# module_tester-v02.net
KiCad netlist of a schematic drawn in EAGLE
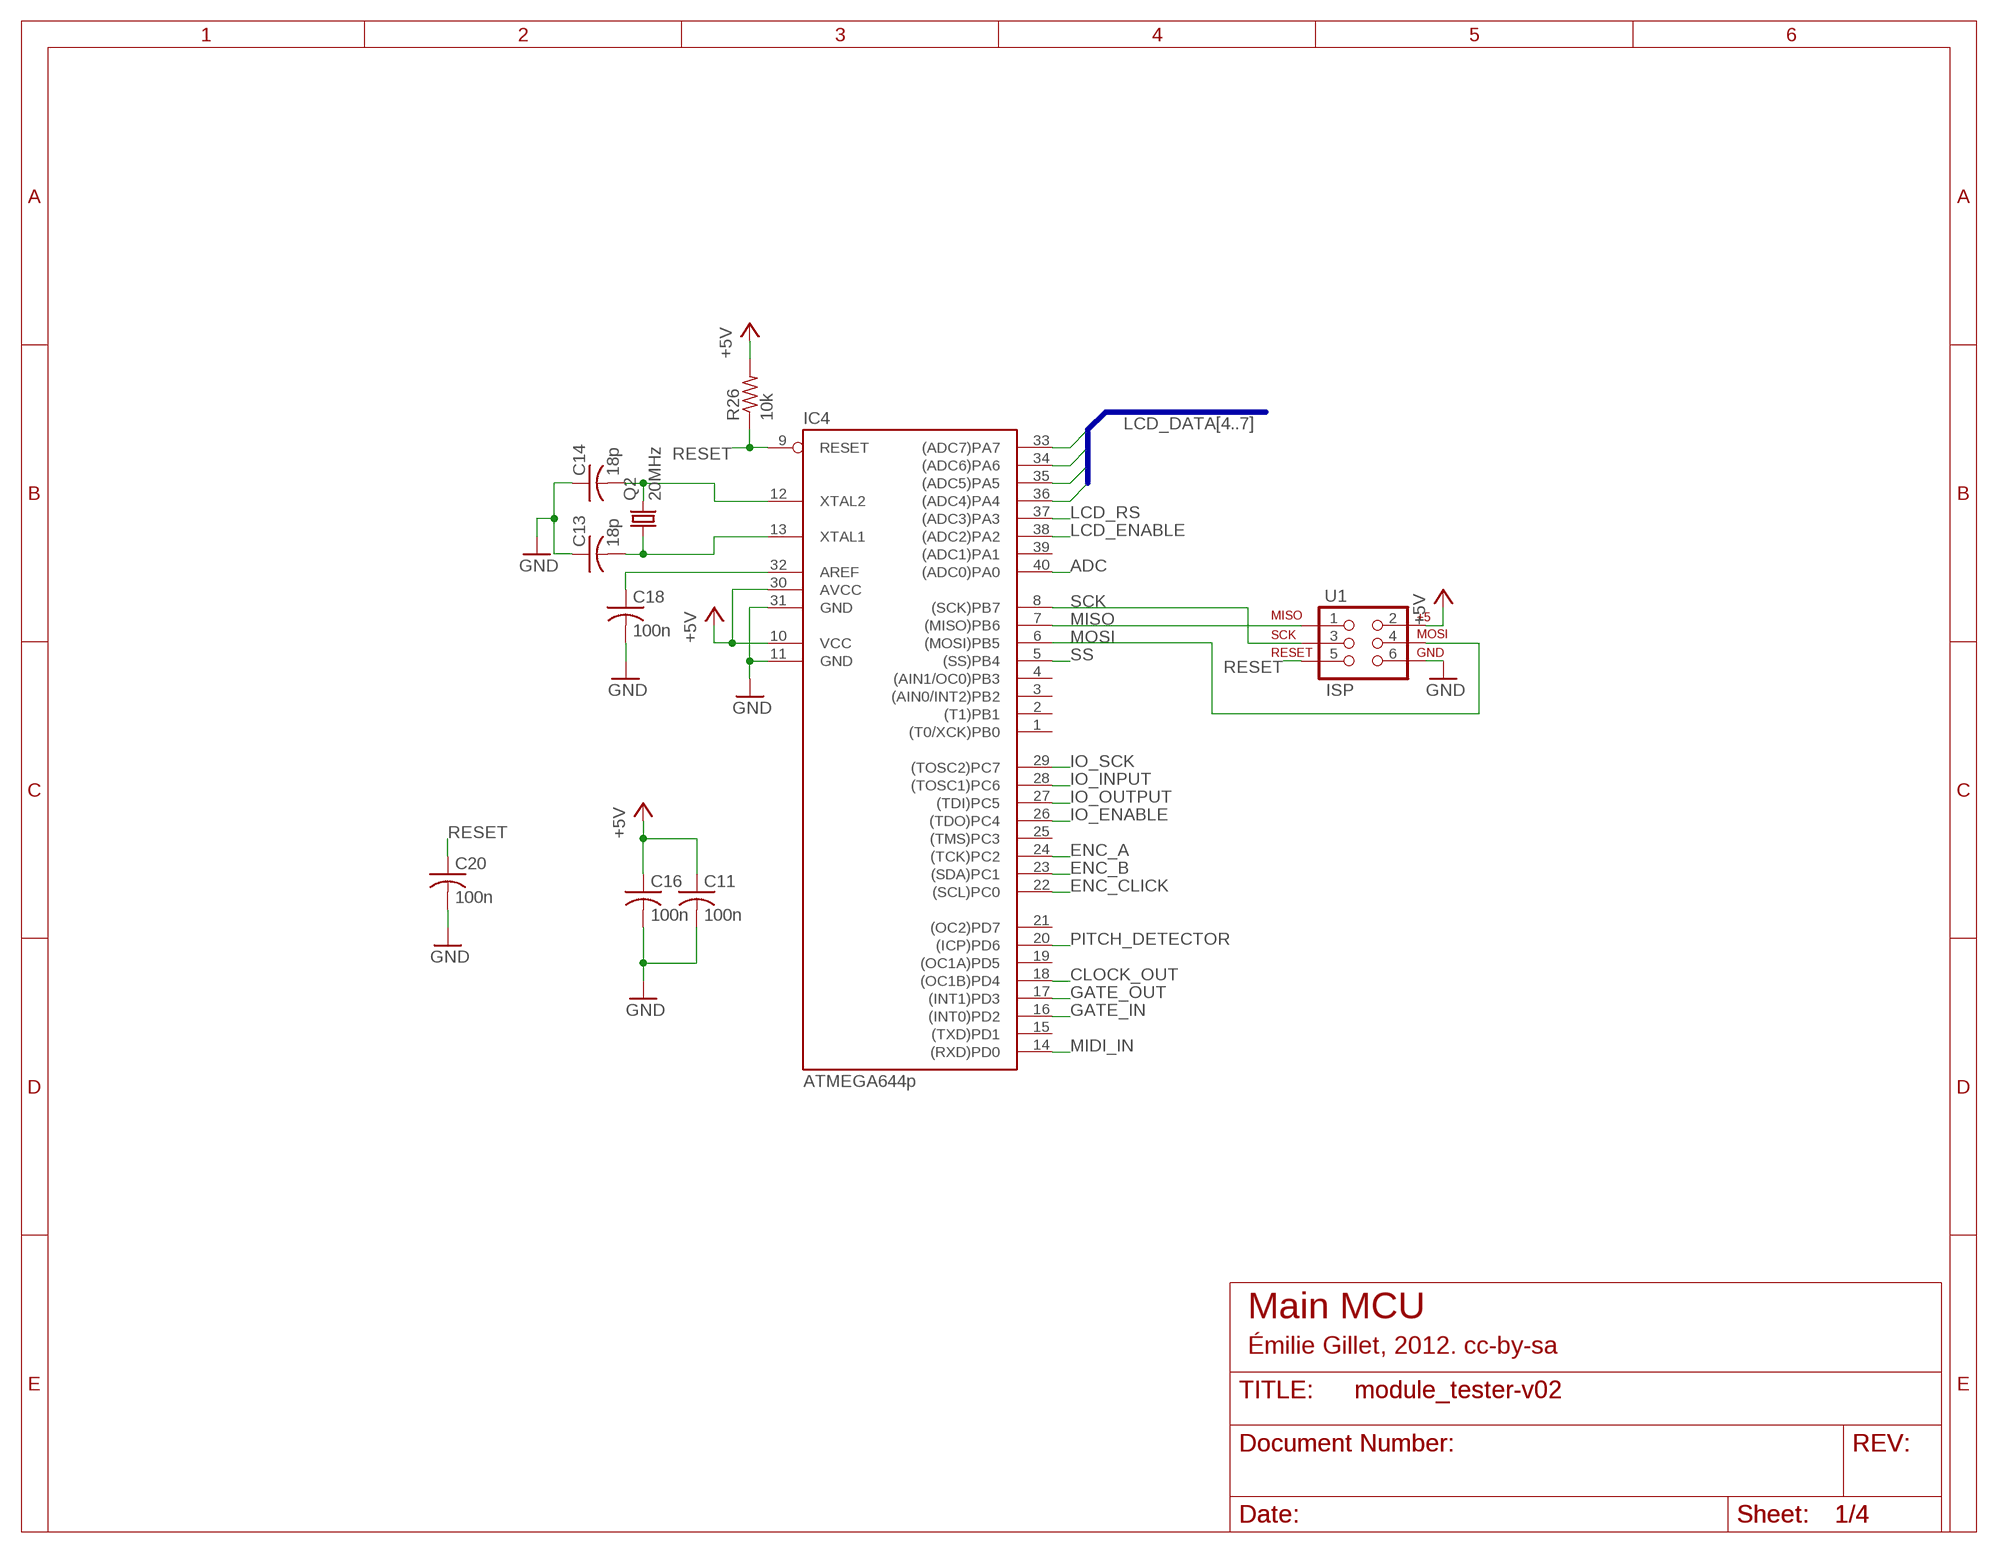
[diagram p0: schematic, sheet 1]
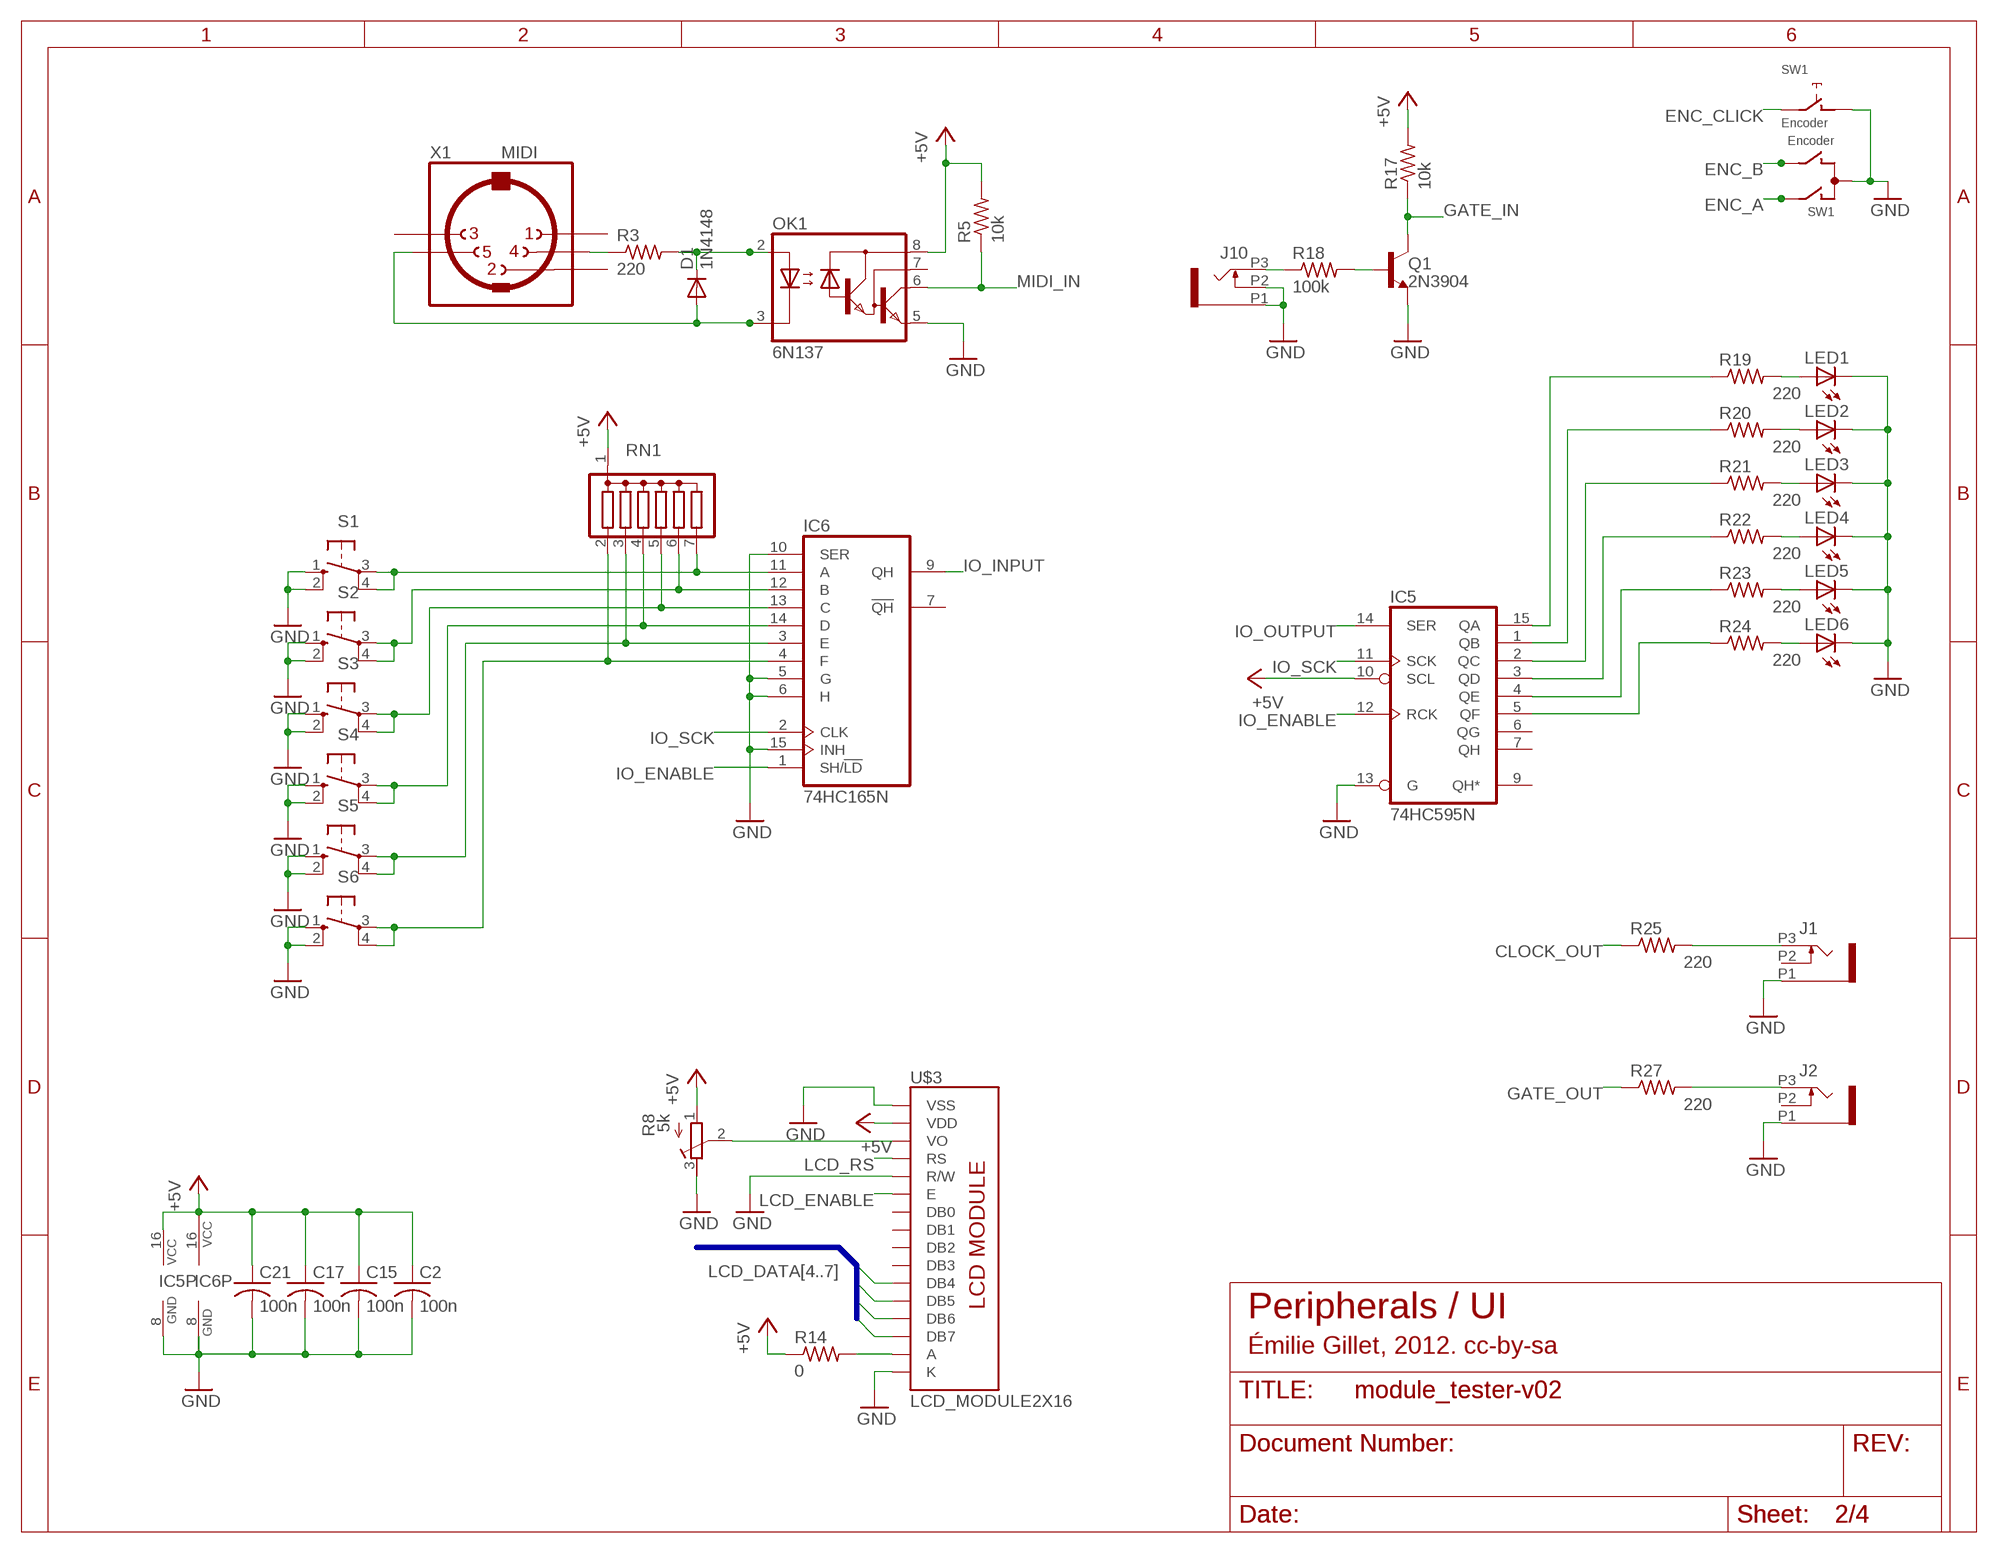
[diagram p1: schematic, sheet 2]
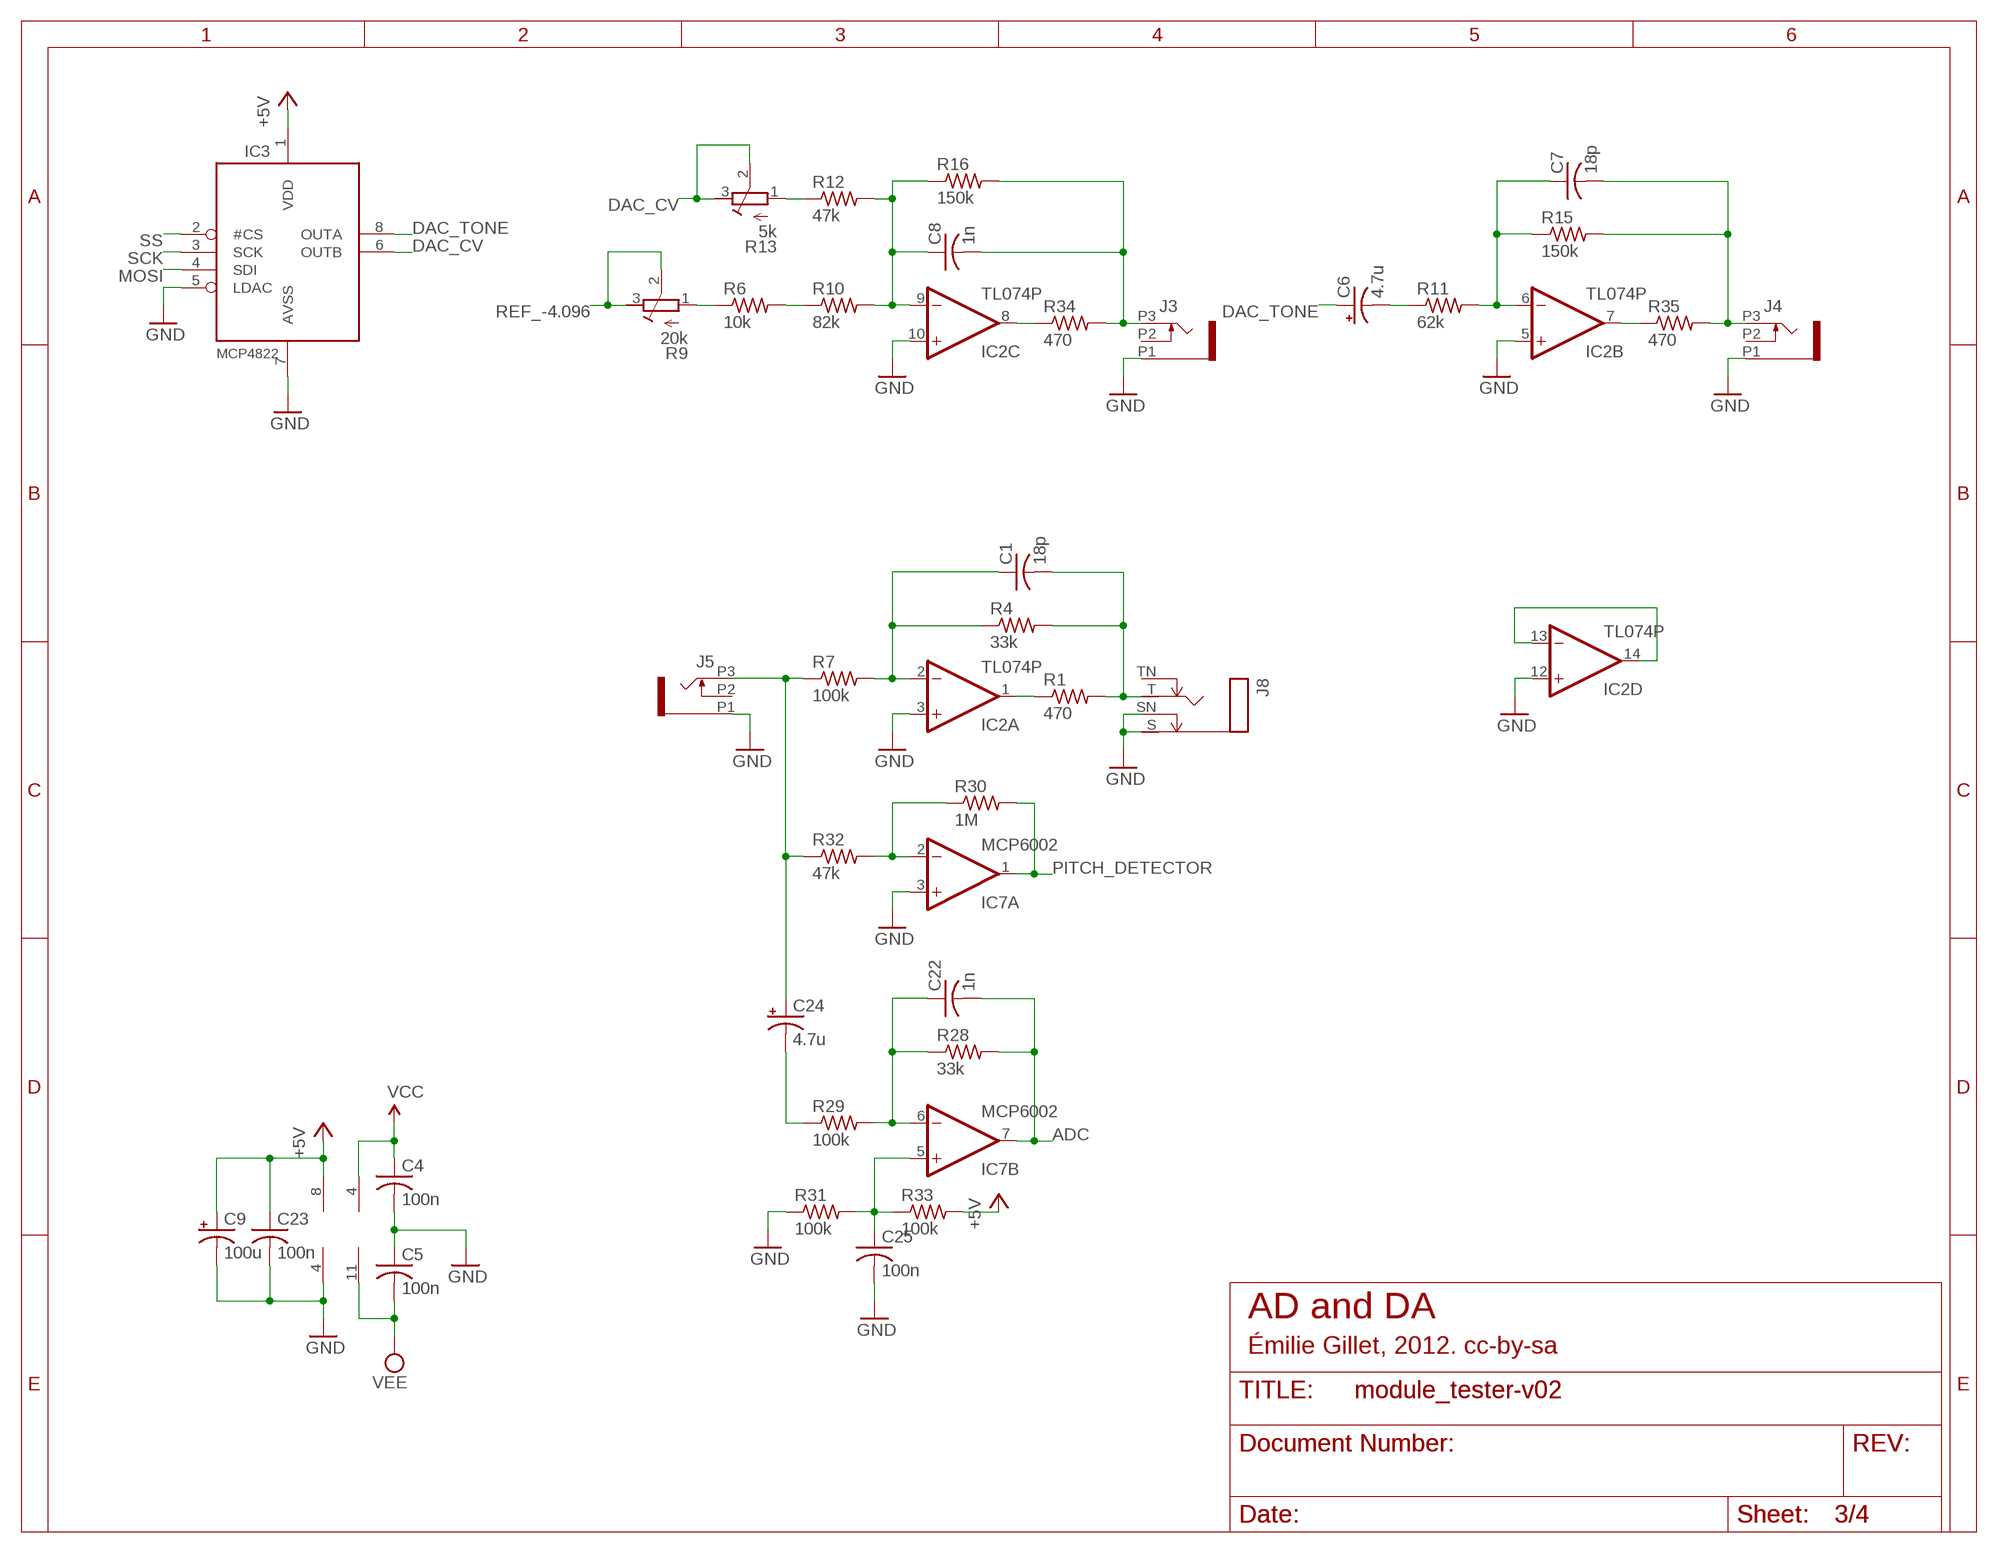
[diagram p2: schematic, sheet 3]
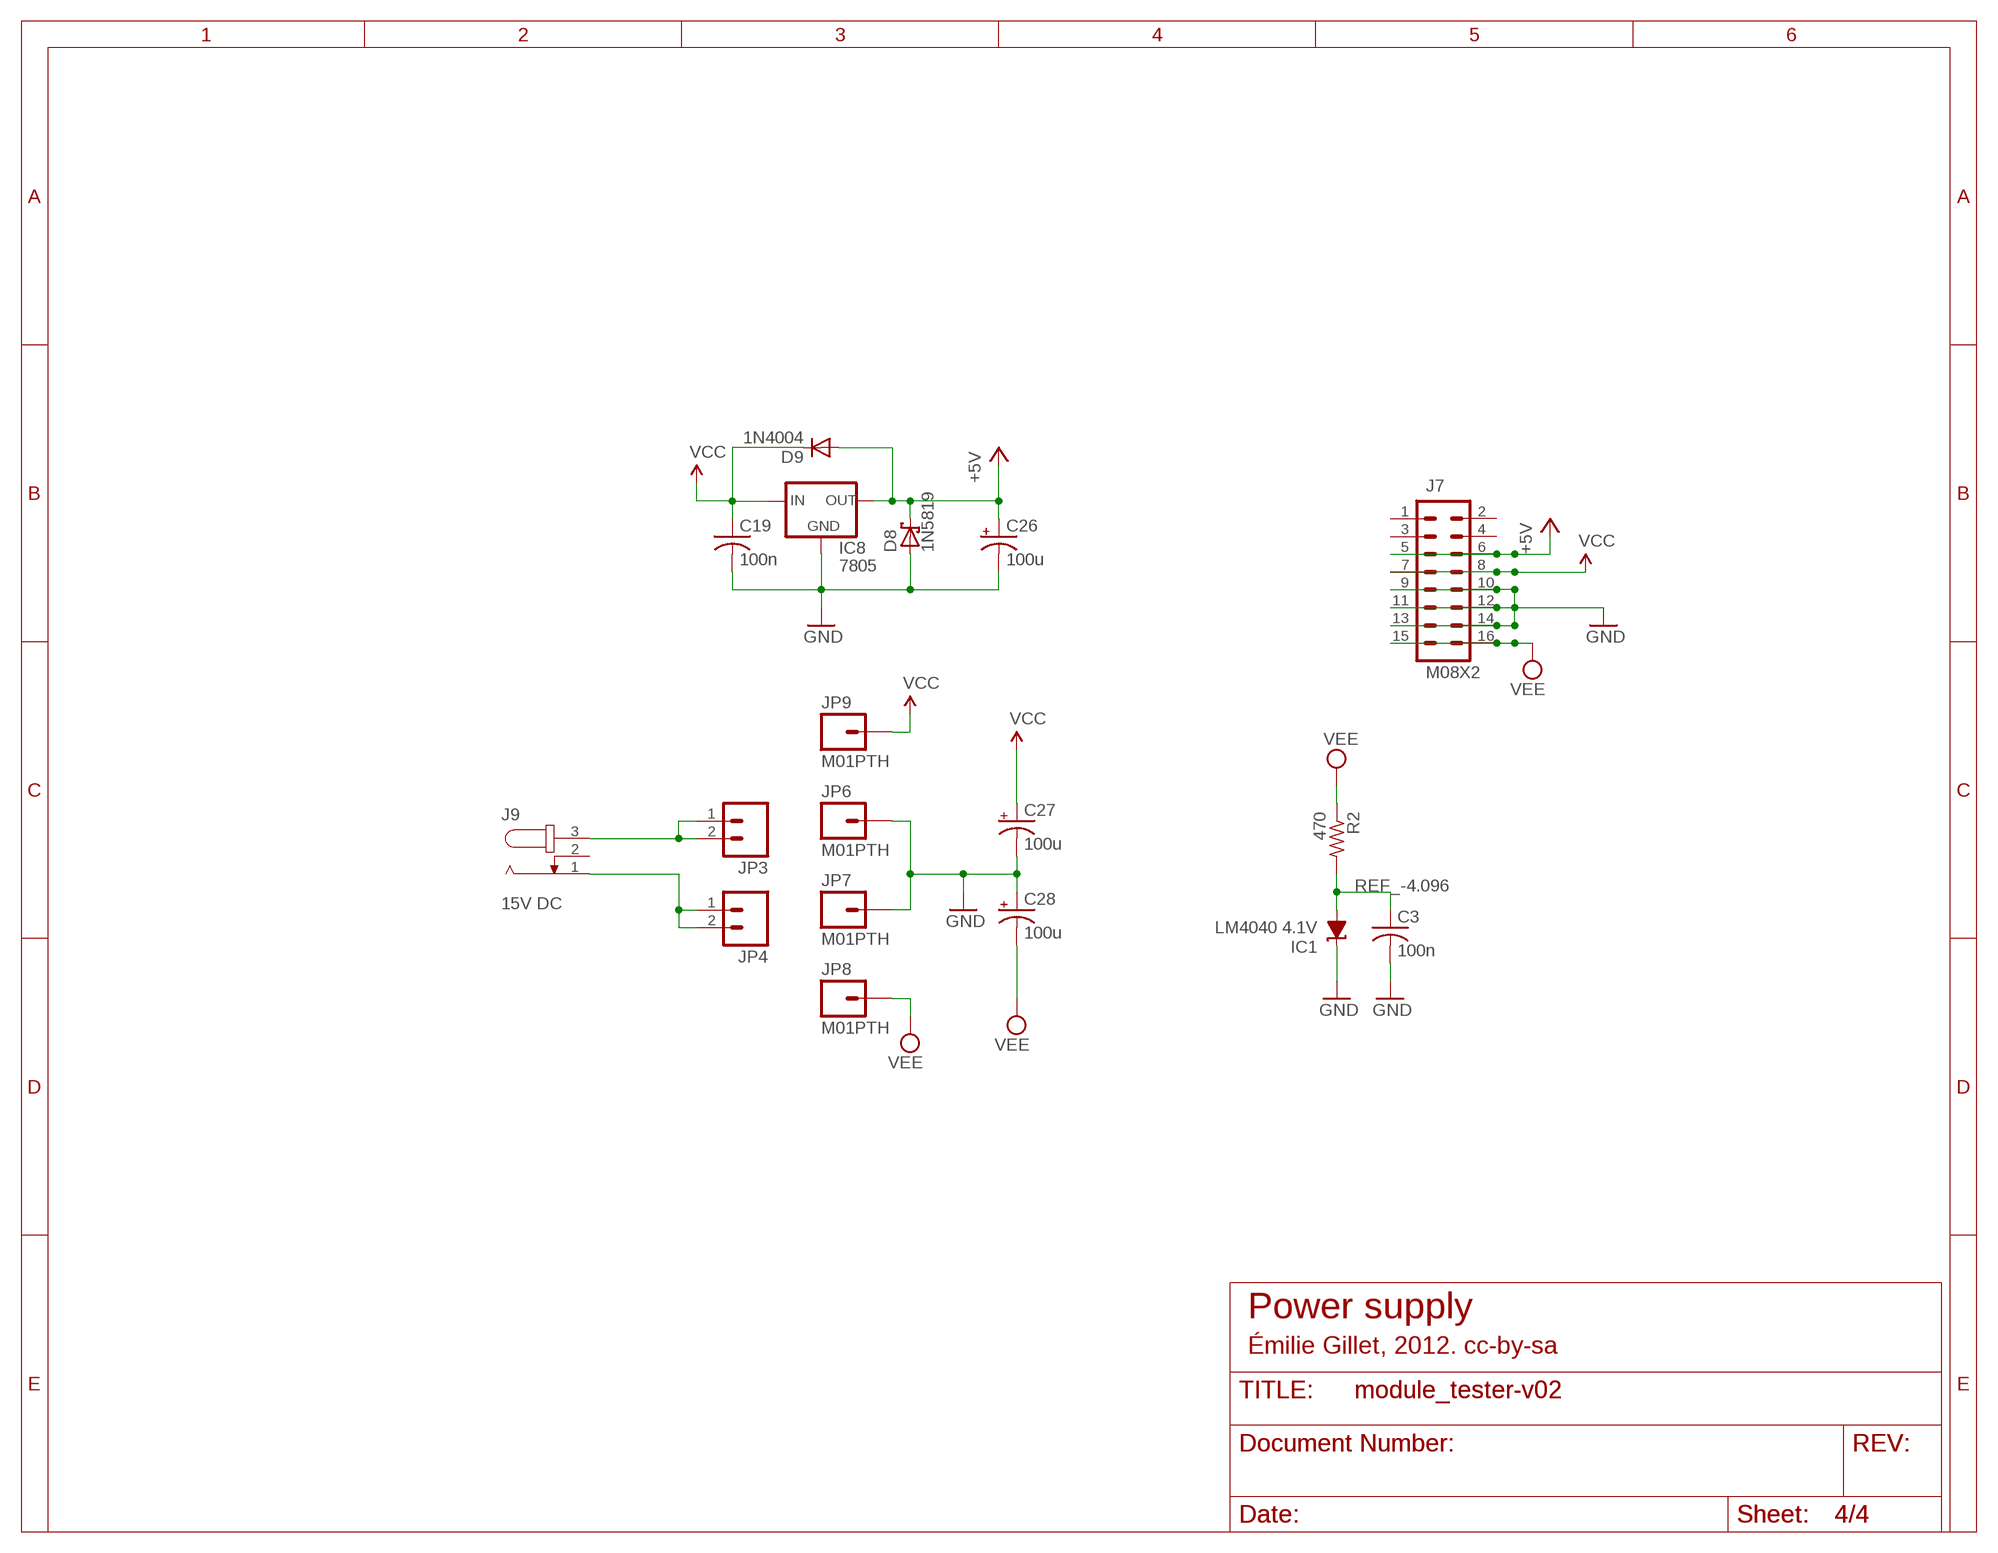
[diagram p3: schematic, sheet 4]

(export (version "E")
  (design (tool "Eeschema 10.0.6"))
  (components
    (comp (ref "C11")
      (value "100n")
      (footprint "eagle-import:C025-025X050")
      (libsource (lib "eagle-import") (part "C-US025-025X050"))
    )
    (comp (ref "C13")
      (value "18p")
      (footprint "eagle-import:C025-025X050")
      (libsource (lib "eagle-import") (part "C-US025-025X050"))
    )
    (comp (ref "C14")
      (value "18p")
      (footprint "eagle-import:C025-025X050")
      (libsource (lib "eagle-import") (part "C-US025-025X050"))
    )
    (comp (ref "C16")
      (value "100n")
      (footprint "eagle-import:C025-025X050")
      (libsource (lib "eagle-import") (part "C-US025-025X050"))
    )
    (comp (ref "C18")
      (value "100n")
      (footprint "eagle-import:C025-025X050")
      (libsource (lib "eagle-import") (part "C-US025-025X050"))
    )
    (comp (ref "C20")
      (value "100n")
      (footprint "eagle-import:C025-025X050")
      (libsource (lib "eagle-import") (part "C-US025-025X050"))
    )
    (comp (ref "IC4")
      (value "ATMEGA644p")
      (footprint "eagle-import:DIL40")
      (libsource (lib "eagle-import") (part "MEGA16-P"))
    )
    (comp (ref "Q2")
      (value "20MHz")
      (footprint "eagle-import:HC49U-V")
      (libsource (lib "eagle-import") (part "CRYSTALHC49U-V"))
    )
    (comp (ref "R26")
      (value "10k")
      (footprint "eagle-import:0204_7")
      (libsource (lib "eagle-import") (part "R-US_0204/7"))
    )
    (comp (ref "U1")
      (value "ISP")
      (footprint "eagle-import:2X3")
      (libsource (lib "eagle-import") (part "AVR_SPI_PRG_6PTH"))
    )
    (comp (ref "C3")
      (value "100n")
      (footprint "eagle-import:C025-025X050")
      (libsource (lib "eagle-import") (part "C-US025-025X050"))
    )
    (comp (ref "C19")
      (value "100n")
      (footprint "eagle-import:C025-025X050")
      (libsource (lib "eagle-import") (part "C-US025-025X050"))
    )
    (comp (ref "C26")
      (value "100u")
      (footprint "eagle-import:E2,5-7")
      (libsource (lib "eagle-import") (part "CPOL-USE2.5-7"))
    )
    (comp (ref "C27")
      (value "100u")
      (footprint "eagle-import:E2,5-7")
      (libsource (lib "eagle-import") (part "CPOL-USE2.5-7"))
    )
    (comp (ref "C28")
      (value "100u")
      (footprint "eagle-import:E2,5-7")
      (libsource (lib "eagle-import") (part "CPOL-USE2.5-7"))
    )
    (comp (ref "D8")
      (value "1N5819")
      (footprint "eagle-import:DO41-7.6")
      (libsource (lib "eagle-import") (part "1N5819-T"))
    )
    (comp (ref "D9")
      (value "1N4004")
      (footprint "eagle-import:DO41-10")
      (libsource (lib "eagle-import") (part "1N4004"))
    )
    (comp (ref "IC1")
      (value "LM4040 4.1V")
      (footprint "eagle-import:LP_O-PBCY-W3")
      (libsource (lib "eagle-import") (part "LM4041LPC12"))
    )
    (comp (ref "IC8")
      (value "7805")
      (footprint "eagle-import:78XXS")
      (libsource (lib "eagle-import") (part "78XXS"))
    )
    (comp (ref "J7")
      (value "M08X2")
      (footprint "eagle-import:2X8")
      (libsource (lib "eagle-import") (part "M08X2"))
    )
    (comp (ref "J9")
      (value "JACK-PLUG2")
      (footprint "eagle-import:SPC4078_BIG_HOLES")
      (libsource (lib "eagle-import") (part "JACK-PLUG2"))
    )
    (comp (ref "JP3")
      (value "M02PTH")
      (footprint "eagle-import:1X02")
      (libsource (lib "eagle-import") (part "M02PTH"))
    )
    (comp (ref "JP4")
      (value "M02PTH")
      (footprint "eagle-import:1X02")
      (libsource (lib "eagle-import") (part "M02PTH"))
    )
    (comp (ref "JP6")
      (value "M01PTH")
      (footprint "eagle-import:1X01")
      (libsource (lib "eagle-import") (part "M01PTH"))
    )
    (comp (ref "JP7")
      (value "M01PTH")
      (footprint "eagle-import:1X01")
      (libsource (lib "eagle-import") (part "M01PTH"))
    )
    (comp (ref "JP8")
      (value "M01PTH")
      (footprint "eagle-import:1X01")
      (libsource (lib "eagle-import") (part "M01PTH"))
    )
    (comp (ref "JP9")
      (value "M01PTH")
      (footprint "eagle-import:1X01")
      (libsource (lib "eagle-import") (part "M01PTH"))
    )
    (comp (ref "R2")
      (value "470")
      (footprint "eagle-import:0204_7")
      (libsource (lib "eagle-import") (part "resistor_R-US_0204/7"))
    )
    (comp (ref "C1")
      (value "18p")
      (footprint "eagle-import:C025-025X050")
      (libsource (lib "eagle-import") (part "C-US025-025X050"))
    )
    (comp (ref "C4")
      (value "100n")
      (footprint "eagle-import:C025-025X050")
      (libsource (lib "eagle-import") (part "C-US025-025X050"))
    )
    (comp (ref "C5")
      (value "100n")
      (footprint "eagle-import:C025-025X050")
      (libsource (lib "eagle-import") (part "C-US025-025X050"))
    )
    (comp (ref "C6")
      (value "4.7u")
      (footprint "eagle-import:E2,5-6")
      (libsource (lib "eagle-import") (part "CPOL-USE2.5-6"))
    )
    (comp (ref "C7")
      (value "18p")
      (footprint "eagle-import:C025-025X050")
      (libsource (lib "eagle-import") (part "C-US025-025X050"))
    )
    (comp (ref "C8")
      (value "1n")
      (footprint "eagle-import:C025-025X050")
      (libsource (lib "eagle-import") (part "C-US025-025X050"))
    )
    (comp (ref "C9")
      (value "100u")
      (footprint "eagle-import:E2,5-7")
      (libsource (lib "eagle-import") (part "CPOL-USE2.5-7"))
    )
    (comp (ref "C22")
      (value "1n")
      (footprint "eagle-import:C025-025X050")
      (libsource (lib "eagle-import") (part "C-US025-025X050"))
    )
    (comp (ref "C23")
      (value "100n")
      (footprint "eagle-import:C025-025X050")
      (libsource (lib "eagle-import") (part "C-US025-025X050"))
    )
    (comp (ref "C24")
      (value "4.7u")
      (footprint "eagle-import:E2,5-6")
      (libsource (lib "eagle-import") (part "CPOL-USE2.5-6"))
    )
    (comp (ref "C25")
      (value "100n")
      (footprint "eagle-import:C025-025X050")
      (libsource (lib "eagle-import") (part "C-US025-025X050"))
    )
    (comp (ref "IC2")
      (value "TL074P")
      (footprint "eagle-import:DIL14")
      (libsource (lib "eagle-import") (part "TL074P"))
    )
    (comp (ref "IC3")
      (value "MCP4822")
      (footprint "eagle-import:DIL08")
      (libsource (lib "eagle-import") (part "MCP4822"))
    )
    (comp (ref "IC7")
      (value "MCP6002")
      (footprint "eagle-import:DIL08")
      (libsource (lib "eagle-import") (part "TL072P"))
    )
    (comp (ref "J3")
      (value "PJ301_THONKICONN6")
      (footprint "eagle-import:WQP_PJ_301M6")
      (libsource (lib "eagle-import") (part "PJ301_THONKICONN6"))
    )
    (comp (ref "J4")
      (value "PJ301_THONKICONN6")
      (footprint "eagle-import:WQP_PJ_301M6")
      (libsource (lib "eagle-import") (part "PJ301_THONKICONN6"))
    )
    (comp (ref "J5")
      (value "PJ301_THONKICONN6")
      (footprint "eagle-import:WQP_PJ_301M6")
      (libsource (lib "eagle-import") (part "PJ301_THONKICONN6"))
    )
    (comp (ref "J8")
      (value "MONOSWSLIM")
      (footprint "eagle-import:NRJ4HF")
      (libsource (lib "eagle-import") (part "MONOSWSLIM"))
    )
    (comp (ref "R1")
      (value "470")
      (footprint "eagle-import:0204_7")
      (libsource (lib "eagle-import") (part "R-US_0204/7"))
    )
    (comp (ref "R4")
      (value "33k")
      (footprint "eagle-import:0204_7")
      (libsource (lib "eagle-import") (part "R-US_0204/7"))
    )
    (comp (ref "R6")
      (value "10k")
      (footprint "eagle-import:0204_7")
      (libsource (lib "eagle-import") (part "R-US_0204/7"))
    )
    (comp (ref "R7")
      (value "100k")
      (footprint "eagle-import:0204_7")
      (libsource (lib "eagle-import") (part "R-US_0204/7"))
    )
    (comp (ref "R9")
      (value "20k")
      (footprint "eagle-import:RTRIM3296W")
      (libsource (lib "eagle-import") (part "R-TRIMM3296W"))
    )
    (comp (ref "R10")
      (value "82k")
      (footprint "eagle-import:0204_7")
      (libsource (lib "eagle-import") (part "R-US_0204/7"))
    )
    (comp (ref "R11")
      (value "62k")
      (footprint "eagle-import:0204_7")
      (libsource (lib "eagle-import") (part "R-US_0204/7"))
    )
    (comp (ref "R12")
      (value "47k")
      (footprint "eagle-import:0204_7")
      (libsource (lib "eagle-import") (part "R-US_0204/7"))
    )
    (comp (ref "R13")
      (value "5k")
      (footprint "eagle-import:RTRIM3296W")
      (libsource (lib "eagle-import") (part "R-TRIMM3296W"))
    )
    (comp (ref "R15")
      (value "150k")
      (footprint "eagle-import:0204_7")
      (libsource (lib "eagle-import") (part "R-US_0204/7"))
    )
    (comp (ref "R16")
      (value "150k")
      (footprint "eagle-import:0204_7")
      (libsource (lib "eagle-import") (part "R-US_0204/7"))
    )
    (comp (ref "R28")
      (value "33k")
      (footprint "eagle-import:0204_7")
      (libsource (lib "eagle-import") (part "R-US_0204/7"))
    )
    (comp (ref "R29")
      (value "100k")
      (footprint "eagle-import:0204_7")
      (libsource (lib "eagle-import") (part "R-US_0204/7"))
    )
    (comp (ref "R30")
      (value "1M")
      (footprint "eagle-import:0204_7")
      (libsource (lib "eagle-import") (part "R-US_0204/7"))
    )
    (comp (ref "R31")
      (value "100k")
      (footprint "eagle-import:0204_7")
      (libsource (lib "eagle-import") (part "R-US_0204/7"))
    )
    (comp (ref "R32")
      (value "47k")
      (footprint "eagle-import:0204_7")
      (libsource (lib "eagle-import") (part "R-US_0204/7"))
    )
    (comp (ref "R33")
      (value "100k")
      (footprint "eagle-import:0204_7")
      (libsource (lib "eagle-import") (part "R-US_0204/7"))
    )
    (comp (ref "R34")
      (value "470")
      (footprint "eagle-import:0204_7")
      (libsource (lib "eagle-import") (part "R-US_0204/7"))
    )
    (comp (ref "R35")
      (value "470")
      (footprint "eagle-import:0204_7")
      (libsource (lib "eagle-import") (part "R-US_0204/7"))
    )
    (comp (ref "C2")
      (value "100n")
      (footprint "eagle-import:C025-025X050")
      (libsource (lib "eagle-import") (part "C-US025-025X050"))
    )
    (comp (ref "C15")
      (value "100n")
      (footprint "eagle-import:C025-025X050")
      (libsource (lib "eagle-import") (part "C-US025-025X050"))
    )
    (comp (ref "C17")
      (value "100n")
      (footprint "eagle-import:C025-025X050")
      (libsource (lib "eagle-import") (part "C-US025-025X050"))
    )
    (comp (ref "C21")
      (value "100n")
      (footprint "eagle-import:C025-025X050")
      (libsource (lib "eagle-import") (part "C-US025-025X050"))
    )
    (comp (ref "D1")
      (value "1N4148")
      (footprint "eagle-import:D-5")
      (libsource (lib "eagle-import") (part "DIODE-D-5"))
    )
    (comp (ref "IC5")
      (value "74HC595N")
      (footprint "eagle-import:DIL16")
      (libsource (lib "eagle-import") (part "74595NHC"))
    )
    (comp (ref "IC6")
      (value "74HC165N")
      (footprint "eagle-import:DIL16")
      (libsource (lib "eagle-import") (part "74165NLS"))
    )
    (comp (ref "J1")
      (value "PJ301_THONKICONN6")
      (footprint "eagle-import:WQP_PJ_301M6")
      (libsource (lib "eagle-import") (part "PJ301_THONKICONN6"))
    )
    (comp (ref "J2")
      (value "PJ301_THONKICONN6")
      (footprint "eagle-import:WQP_PJ_301M6")
      (libsource (lib "eagle-import") (part "PJ301_THONKICONN6"))
    )
    (comp (ref "J10")
      (value "PJ301_THONKICONN6")
      (footprint "eagle-import:WQP_PJ_301M6")
      (libsource (lib "eagle-import") (part "PJ301_THONKICONN6"))
    )
    (comp (ref "LED1")
      (value "LED3MM")
      (footprint "eagle-import:LED3MM")
      (libsource (lib "eagle-import") (part "LED3MM"))
    )
    (comp (ref "LED2")
      (value "LED3MM")
      (footprint "eagle-import:LED3MM")
      (libsource (lib "eagle-import") (part "LED3MM"))
    )
    (comp (ref "LED3")
      (value "LED3MM")
      (footprint "eagle-import:LED3MM")
      (libsource (lib "eagle-import") (part "LED3MM"))
    )
    (comp (ref "LED4")
      (value "LED3MM")
      (footprint "eagle-import:LED3MM")
      (libsource (lib "eagle-import") (part "LED3MM"))
    )
    (comp (ref "LED5")
      (value "LED3MM")
      (footprint "eagle-import:LED3MM")
      (libsource (lib "eagle-import") (part "LED3MM"))
    )
    (comp (ref "LED6")
      (value "LED3MM")
      (footprint "eagle-import:LED3MM")
      (libsource (lib "eagle-import") (part "LED3MM"))
    )
    (comp (ref "OK1")
      (value "6N137")
      (footprint "eagle-import:DIL08")
      (libsource (lib "eagle-import") (part "6N138"))
    )
    (comp (ref "Q1")
      (value "2N3904")
      (footprint "eagle-import:TO92-")
      (libsource (lib "eagle-import") (part "2N3904"))
    )
    (comp (ref "R3")
      (value "220")
      (footprint "eagle-import:0204_7")
      (libsource (lib "eagle-import") (part "R-US_0204/7"))
    )
    (comp (ref "R5")
      (value "10k")
      (footprint "eagle-import:0204_7")
      (libsource (lib "eagle-import") (part "R-US_0204/7"))
    )
    (comp (ref "R8")
      (value "5k")
      (footprint "eagle-import:RTRIM3339P")
      (libsource (lib "eagle-import") (part "R-TRIMM3339P"))
    )
    (comp (ref "R14")
      (value "0")
      (footprint "eagle-import:0204_7")
      (libsource (lib "eagle-import") (part "R-US_0204/7"))
    )
    (comp (ref "R17")
      (value "10k")
      (footprint "eagle-import:0204_7")
      (libsource (lib "eagle-import") (part "R-US_0204/7"))
    )
    (comp (ref "R18")
      (value "100k")
      (footprint "eagle-import:0204_7")
      (libsource (lib "eagle-import") (part "R-US_0204/7"))
    )
    (comp (ref "R19")
      (value "220")
      (footprint "eagle-import:0204_7")
      (libsource (lib "eagle-import") (part "R-US_0204/7"))
    )
    (comp (ref "R20")
      (value "220")
      (footprint "eagle-import:0204_7")
      (libsource (lib "eagle-import") (part "R-US_0204/7"))
    )
    (comp (ref "R21")
      (value "220")
      (footprint "eagle-import:0204_7")
      (libsource (lib "eagle-import") (part "R-US_0204/7"))
    )
    (comp (ref "R22")
      (value "220")
      (footprint "eagle-import:0204_7")
      (libsource (lib "eagle-import") (part "R-US_0204/7"))
    )
    (comp (ref "R23")
      (value "220")
      (footprint "eagle-import:0204_7")
      (libsource (lib "eagle-import") (part "R-US_0204/7"))
    )
    (comp (ref "R24")
      (value "220")
      (footprint "eagle-import:0204_7")
      (libsource (lib "eagle-import") (part "R-US_0204/7"))
    )
    (comp (ref "R25")
      (value "220")
      (footprint "eagle-import:0204_7")
      (libsource (lib "eagle-import") (part "R-US_0204/7"))
    )
    (comp (ref "R27")
      (value "220")
      (footprint "eagle-import:0204_7")
      (libsource (lib "eagle-import") (part "R-US_0204/7"))
    )
    (comp (ref "RN1")
      (value "G06R")
      (footprint "eagle-import:SIL7")
      (libsource (lib "eagle-import") (part "G06R"))
    )
    (comp (ref "S1")
      (value "40-XX")
      (footprint "eagle-import:B3F-40XX")
      (libsource (lib "eagle-import") (part "40-XX"))
    )
    (comp (ref "S2")
      (value "40-XX")
      (footprint "eagle-import:B3F-40XX")
      (libsource (lib "eagle-import") (part "40-XX"))
    )
    (comp (ref "S3")
      (value "40-XX")
      (footprint "eagle-import:B3F-40XX")
      (libsource (lib "eagle-import") (part "40-XX"))
    )
    (comp (ref "S4")
      (value "40-XX")
      (footprint "eagle-import:B3F-40XX")
      (libsource (lib "eagle-import") (part "40-XX"))
    )
    (comp (ref "S5")
      (value "40-XX")
      (footprint "eagle-import:B3F-40XX")
      (libsource (lib "eagle-import") (part "40-XX"))
    )
    (comp (ref "S6")
      (value "40-XX")
      (footprint "eagle-import:B3F-40XX")
      (libsource (lib "eagle-import") (part "40-XX"))
    )
    (comp (ref "SW1")
      (value "Encoder")
      (footprint "eagle-import:ALPS_EC12E_SW")
      (libsource (lib "eagle-import") (part "EC12E_SW"))
    )
    (comp (ref "U$3")
      (value "LCD_MODULE2X16")
      (footprint "eagle-import:LCD_MODULE_2X16")
      (libsource (lib "eagle-import") (part "LCD_MODULE2X16"))
    )
    (comp (ref "X1")
      (value "MIDI")
      (footprint "eagle-import:MAB5SH")
      (libsource (lib "eagle-import") (part "MAB5SH"))
    )
  )
  (nets
    (net (code "1") (name "+5V") (class "Default")
      (node (ref "C11") (pin "1") (pinfunction "1_1") (pintype "passive"))
      (node (ref "C15") (pin "1") (pinfunction "1_1") (pintype "passive"))
      (node (ref "C16") (pin "1") (pinfunction "1_1") (pintype "passive"))
      (node (ref "C17") (pin "1") (pinfunction "1_1") (pintype "passive"))
      (node (ref "C2") (pin "1") (pinfunction "1_1") (pintype "passive"))
      (node (ref "C21") (pin "1") (pinfunction "1_1") (pintype "passive"))
      (node (ref "C23") (pin "1") (pinfunction "1_1") (pintype "passive"))
      (node (ref "C26") (pin "+") (pinfunction "+_+") (pintype "passive"))
      (node (ref "C9") (pin "+") (pinfunction "+_+") (pintype "passive"))
      (node (ref "D8") (pin "C") (pinfunction "C_C") (pintype "passive"))
      (node (ref "D9") (pin "A") (pinfunction "A_A") (pintype "passive"))
      (node (ref "IC3") (pin "1") (pinfunction "VDD_1") (pintype "power_in"))
      (node (ref "IC4") (pin "10") (pinfunction "VCC_10") (pintype "power_in"))
      (node (ref "IC4") (pin "30") (pinfunction "AVCC_30") (pintype "power_in"))
      (node (ref "IC5") (pin "10") (pinfunction "SCL_10") (pintype "input"))
      (node (ref "IC5") (pin "16") (pinfunction "VCC_16") (pintype "power_in"))
      (node (ref "IC6") (pin "16") (pinfunction "VCC_16") (pintype "power_in"))
      (node (ref "IC7") (pin "8") (pinfunction "V+_8") (pintype "power_in"))
      (node (ref "IC8") (pin "OUT") (pinfunction "OUT_OUT") (pintype "passive"))
      (node (ref "J7") (pin "5") (pinfunction "5_5") (pintype "passive"))
      (node (ref "J7") (pin "6") (pinfunction "6_6") (pintype "passive"))
      (node (ref "OK1") (pin "8") (pinfunction "VCC_8") (pintype "passive"))
      (node (ref "R14") (pin "1") (pinfunction "1_1") (pintype "passive"))
      (node (ref "R17") (pin "2") (pinfunction "2_2") (pintype "passive"))
      (node (ref "R26") (pin "2") (pinfunction "2_2") (pintype "passive"))
      (node (ref "R33") (pin "2") (pinfunction "2_2") (pintype "passive"))
      (node (ref "R5") (pin "2") (pinfunction "2_2") (pintype "passive"))
      (node (ref "R8") (pin "1") (pinfunction "E_1") (pintype "passive"))
      (node (ref "RN1") (pin "1") (pinfunction "1_1") (pintype "passive"))
      (node (ref "U$3") (pin "2") (pinfunction "VDD_2") (pintype "power_in"))
      (node (ref "U1") (pin "2") (pinfunction "2_2") (pintype "passive"))
    )
    (net (code "4") (name "ADC") (class "Default")
      (node (ref "C22") (pin "2") (pinfunction "2_2") (pintype "passive"))
      (node (ref "IC4") (pin "40") (pinfunction "(ADC0)PA0_40") (pintype "bidirectional"))
      (node (ref "IC7") (pin "7") (pinfunction "OUT_7") (pintype "output"))
      (node (ref "R28") (pin "2") (pinfunction "2_2") (pintype "passive"))
    )
    (net (code "5") (name "CLOCK_OUT") (class "Default")
      (node (ref "IC4") (pin "18") (pinfunction "(OC1B)PD4_18") (pintype "bidirectional"))
      (node (ref "R25") (pin "1") (pinfunction "1_1") (pintype "passive"))
    )
    (net (code "6") (name "DAC_CV") (class "Default")
      (node (ref "IC3") (pin "6") (pinfunction "OUTB_6") (pintype "output"))
      (node (ref "R13") (pin "2") (pinfunction "S_2") (pintype "passive"))
      (node (ref "R13") (pin "3") (pinfunction "A_3") (pintype "passive"))
    )
    (net (code "7") (name "DAC_TONE") (class "Default")
      (node (ref "C6") (pin "+") (pinfunction "+_+") (pintype "passive"))
      (node (ref "IC3") (pin "8") (pinfunction "OUTA_8") (pintype "output"))
    )
    (net (code "8") (name "ENC_A") (class "Default")
      (node (ref "IC4") (pin "24") (pinfunction "(TCK)PC2_24") (pintype "bidirectional"))
      (node (ref "SW1") (pin "A") (pinfunction "A_A") (pintype "passive"))
    )
    (net (code "9") (name "ENC_B") (class "Default")
      (node (ref "IC4") (pin "23") (pinfunction "(SDA)PC1_23") (pintype "bidirectional"))
      (node (ref "SW1") (pin "B") (pinfunction "B_B") (pintype "passive"))
    )
    (net (code "10") (name "ENC_CLICK") (class "Default")
      (node (ref "IC4") (pin "22") (pinfunction "(SCL)PC0_22") (pintype "bidirectional"))
      (node (ref "SW1") (pin "E") (pinfunction "2_E") (pintype "passive"))
    )
    (net (code "11") (name "GATE_IN") (class "Default")
      (node (ref "IC4") (pin "16") (pinfunction "(INT0)PD2_16") (pintype "bidirectional"))
      (node (ref "Q1") (pin "1") (pinfunction "C_1") (pintype "passive"))
      (node (ref "R17") (pin "1") (pinfunction "1_1") (pintype "passive"))
    )
    (net (code "12") (name "GATE_OUT") (class "Default")
      (node (ref "IC4") (pin "17") (pinfunction "(INT1)PD3_17") (pintype "bidirectional"))
      (node (ref "R27") (pin "1") (pinfunction "1_1") (pintype "passive"))
    )
    (net (code "13") (name "GND") (class "Default")
      (node (ref "C11") (pin "2") (pinfunction "2_2") (pintype "passive"))
      (node (ref "C13") (pin "1") (pinfunction "1_1") (pintype "passive"))
      (node (ref "C14") (pin "1") (pinfunction "1_1") (pintype "passive"))
      (node (ref "C15") (pin "2") (pinfunction "2_2") (pintype "passive"))
      (node (ref "C16") (pin "2") (pinfunction "2_2") (pintype "passive"))
      (node (ref "C17") (pin "2") (pinfunction "2_2") (pintype "passive"))
      (node (ref "C18") (pin "2") (pinfunction "2_2") (pintype "passive"))
      (node (ref "C19") (pin "2") (pinfunction "2_2") (pintype "passive"))
      (node (ref "C2") (pin "2") (pinfunction "2_2") (pintype "passive"))
      (node (ref "C20") (pin "2") (pinfunction "2_2") (pintype "passive"))
      (node (ref "C21") (pin "2") (pinfunction "2_2") (pintype "passive"))
      (node (ref "C23") (pin "2") (pinfunction "2_2") (pintype "passive"))
      (node (ref "C25") (pin "2") (pinfunction "2_2") (pintype "passive"))
      (node (ref "C26") (pin "-") (pinfunction "-_-") (pintype "passive"))
      (node (ref "C27") (pin "-") (pinfunction "-_-") (pintype "passive"))
      (node (ref "C28") (pin "+") (pinfunction "+_+") (pintype "passive"))
      (node (ref "C3") (pin "2") (pinfunction "2_2") (pintype "passive"))
      (node (ref "C4") (pin "2") (pinfunction "2_2") (pintype "passive"))
      (node (ref "C5") (pin "1") (pinfunction "1_1") (pintype "passive"))
      (node (ref "C9") (pin "-") (pinfunction "-_-") (pintype "passive"))
      (node (ref "D8") (pin "A") (pinfunction "A_A") (pintype "passive"))
      (node (ref "IC1") (pin "2") (pinfunction "C_2") (pintype "passive"))
      (node (ref "IC2") (pin "10") (pinfunction "+IN_10") (pintype "input"))
      (node (ref "IC2") (pin "12") (pinfunction "+IN_12") (pintype "input"))
      (node (ref "IC2") (pin "3") (pinfunction "+IN_3") (pintype "input"))
      (node (ref "IC2") (pin "5") (pinfunction "+IN_5") (pintype "input"))
      (node (ref "IC3") (pin "5") (pinfunction "LDAC_5") (pintype "input"))
      (node (ref "IC3") (pin "7") (pinfunction "AVSS_7") (pintype "power_in"))
      (node (ref "IC4") (pin "11") (pinfunction "GND_11") (pintype "power_in"))
      (node (ref "IC4") (pin "31") (pinfunction "GND_31") (pintype "power_in"))
      (node (ref "IC5") (pin "13") (pinfunction "G_13") (pintype "input"))
      (node (ref "IC5") (pin "8") (pinfunction "GND_8") (pintype "power_in"))
      (node (ref "IC6") (pin "10") (pinfunction "SER_10") (pintype "input"))
      (node (ref "IC6") (pin "15") (pinfunction "INH_15") (pintype "input"))
      (node (ref "IC6") (pin "5") (pinfunction "G_5") (pintype "input"))
      (node (ref "IC6") (pin "6") (pinfunction "H_6") (pintype "input"))
      (node (ref "IC6") (pin "8") (pinfunction "GND_8") (pintype "power_in"))
      (node (ref "IC7") (pin "3") (pinfunction "+IN_3") (pintype "input"))
      (node (ref "IC7") (pin "4") (pinfunction "V-_4") (pintype "power_in"))
      (node (ref "IC8") (pin "GND") (pinfunction "GND_GND") (pintype "input"))
      (node (ref "J1") (pin "P1") (pinfunction "1_P1") (pintype "passive"))
      (node (ref "J10") (pin "P1") (pinfunction "1_P1") (pintype "passive"))
      (node (ref "J10") (pin "P2") (pinfunction "2_P2") (pintype "passive"))
      (node (ref "J2") (pin "P1") (pinfunction "1_P1") (pintype "passive"))
      (node (ref "J3") (pin "P1") (pinfunction "1_P1") (pintype "passive"))
      (node (ref "J4") (pin "P1") (pinfunction "1_P1") (pintype "passive"))
      (node (ref "J5") (pin "P1") (pinfunction "1_P1") (pintype "passive"))
      (node (ref "J7") (pin "10") (pinfunction "10_10") (pintype "passive"))
      (node (ref "J7") (pin "11") (pinfunction "11_11") (pintype "passive"))
      (node (ref "J7") (pin "12") (pinfunction "12_12") (pintype "passive"))
      (node (ref "J7") (pin "13") (pinfunction "13_13") (pintype "passive"))
      (node (ref "J7") (pin "14") (pinfunction "14_14") (pintype "passive"))
      (node (ref "J7") (pin "9") (pinfunction "9_9") (pintype "passive"))
      (node (ref "J8") (pin "S") (pinfunction "S_S") (pintype "passive"))
      (node (ref "J8") (pin "SN") (pinfunction "SN_SN") (pintype "passive"))
      (node (ref "JP6") (pin "1") (pinfunction "1_1") (pintype "passive"))
      (node (ref "JP7") (pin "1") (pinfunction "1_1") (pintype "passive"))
      (node (ref "LED1") (pin "K") (pinfunction "C_K") (pintype "passive"))
      (node (ref "LED2") (pin "K") (pinfunction "C_K") (pintype "passive"))
      (node (ref "LED3") (pin "K") (pinfunction "C_K") (pintype "passive"))
      (node (ref "LED4") (pin "K") (pinfunction "C_K") (pintype "passive"))
      (node (ref "LED5") (pin "K") (pinfunction "C_K") (pintype "passive"))
      (node (ref "LED6") (pin "K") (pinfunction "C_K") (pintype "passive"))
      (node (ref "OK1") (pin "5") (pinfunction "GND_5") (pintype "passive"))
      (node (ref "Q1") (pin "3") (pinfunction "E_3") (pintype "passive"))
      (node (ref "R31") (pin "1") (pinfunction "1_1") (pintype "passive"))
      (node (ref "R8") (pin "3") (pinfunction "A_3") (pintype "passive"))
      (node (ref "S1") (pin "1") (pinfunction "S_1") (pintype "passive"))
      (node (ref "S1") (pin "2") (pinfunction "S1_2") (pintype "passive"))
      (node (ref "S2") (pin "1") (pinfunction "S_1") (pintype "passive"))
      (node (ref "S2") (pin "2") (pinfunction "S1_2") (pintype "passive"))
      (node (ref "S3") (pin "1") (pinfunction "S_1") (pintype "passive"))
      (node (ref "S3") (pin "2") (pinfunction "S1_2") (pintype "passive"))
      (node (ref "S4") (pin "1") (pinfunction "S_1") (pintype "passive"))
      (node (ref "S4") (pin "2") (pinfunction "S1_2") (pintype "passive"))
      (node (ref "S5") (pin "1") (pinfunction "S_1") (pintype "passive"))
      (node (ref "S5") (pin "2") (pinfunction "S1_2") (pintype "passive"))
      (node (ref "S6") (pin "1") (pinfunction "S_1") (pintype "passive"))
      (node (ref "S6") (pin "2") (pinfunction "S1_2") (pintype "passive"))
      (node (ref "SW1") (pin "C") (pinfunction "C_C") (pintype "passive"))
      (node (ref "SW1") (pin "D") (pinfunction "1_D") (pintype "passive"))
      (node (ref "U$3") (pin "1") (pinfunction "VSS_1") (pintype "power_in"))
      (node (ref "U$3") (pin "16") (pinfunction "K_16") (pintype "power_in"))
      (node (ref "U$3") (pin "5") (pinfunction "R/W_5") (pintype "input"))
      (node (ref "U1") (pin "6") (pinfunction "6_6") (pintype "passive"))
    )
    (net (code "14") (name "IO_ENABLE") (class "Default")
      (node (ref "IC4") (pin "26") (pinfunction "(TDO)PC4_26") (pintype "bidirectional"))
      (node (ref "IC5") (pin "12") (pinfunction "RCK_12") (pintype "input"))
      (node (ref "IC6") (pin "1") (pinfunction "SH/~{LD}_1") (pintype "input"))
    )
    (net (code "15") (name "IO_INPUT") (class "Default")
      (node (ref "IC4") (pin "28") (pinfunction "(TOSC1)PC6_28") (pintype "bidirectional"))
      (node (ref "IC6") (pin "9") (pinfunction "QH_9") (pintype "output"))
    )
    (net (code "16") (name "IO_OUTPUT") (class "Default")
      (node (ref "IC4") (pin "27") (pinfunction "(TDI)PC5_27") (pintype "bidirectional"))
      (node (ref "IC5") (pin "14") (pinfunction "SER_14") (pintype "input"))
    )
    (net (code "17") (name "IO_SCK") (class "Default")
      (node (ref "IC4") (pin "29") (pinfunction "(TOSC2)PC7_29") (pintype "bidirectional"))
      (node (ref "IC5") (pin "11") (pinfunction "SCK_11") (pintype "input"))
      (node (ref "IC6") (pin "2") (pinfunction "CLK_2") (pintype "input"))
    )
    (net (code "18") (name "LCD_DATA4") (class "Default")
      (node (ref "IC4") (pin "36") (pinfunction "(ADC4)PA4_36") (pintype "bidirectional"))
      (node (ref "U$3") (pin "11") (pinfunction "DB4_11") (pintype "bidirectional"))
    )
    (net (code "19") (name "LCD_DATA5") (class "Default")
      (node (ref "IC4") (pin "35") (pinfunction "(ADC5)PA5_35") (pintype "bidirectional"))
      (node (ref "U$3") (pin "12") (pinfunction "DB5_12") (pintype "bidirectional"))
    )
    (net (code "20") (name "LCD_DATA6") (class "Default")
      (node (ref "IC4") (pin "34") (pinfunction "(ADC6)PA6_34") (pintype "bidirectional"))
      (node (ref "U$3") (pin "13") (pinfunction "DB6_13") (pintype "bidirectional"))
    )
    (net (code "21") (name "LCD_DATA7") (class "Default")
      (node (ref "IC4") (pin "33") (pinfunction "(ADC7)PA7_33") (pintype "bidirectional"))
      (node (ref "U$3") (pin "14") (pinfunction "DB7_14") (pintype "bidirectional"))
    )
    (net (code "22") (name "LCD_ENABLE") (class "Default")
      (node (ref "IC4") (pin "38") (pinfunction "(ADC2)PA2_38") (pintype "bidirectional"))
      (node (ref "U$3") (pin "6") (pinfunction "E_6") (pintype "input"))
    )
    (net (code "23") (name "LCD_RS") (class "Default")
      (node (ref "IC4") (pin "37") (pinfunction "(ADC3)PA3_37") (pintype "bidirectional"))
      (node (ref "U$3") (pin "4") (pinfunction "RS_4") (pintype "input"))
    )
    (net (code "24") (name "MIDI_IN") (class "Default")
      (node (ref "IC4") (pin "14") (pinfunction "(RXD)PD0_14") (pintype "bidirectional"))
      (node (ref "OK1") (pin "6") (pinfunction "VO_6") (pintype "passive"))
      (node (ref "R5") (pin "1") (pinfunction "1_1") (pintype "passive"))
    )
    (net (code "25") (name "MISO") (class "Default")
      (node (ref "IC4") (pin "7") (pinfunction "(MISO)PB6_7") (pintype "bidirectional"))
      (node (ref "U1") (pin "1") (pinfunction "1_1") (pintype "passive"))
    )
    (net (code "26") (name "MOSI") (class "Default")
      (node (ref "IC3") (pin "4") (pinfunction "SDI_4") (pintype "input"))
      (node (ref "IC4") (pin "6") (pinfunction "(MOSI)PB5_6") (pintype "bidirectional"))
      (node (ref "U1") (pin "4") (pinfunction "4_4") (pintype "passive"))
    )
    (net (code "27") (name "Net-(C1-Pad2)") (class "Default")
      (node (ref "C1") (pin "2") (pinfunction "2_2") (pintype "passive"))
      (node (ref "J8") (pin "T") (pinfunction "T_T") (pintype "passive"))
      (node (ref "R1") (pin "2") (pinfunction "2_2") (pintype "passive"))
      (node (ref "R4") (pin "2") (pinfunction "2_2") (pintype "passive"))
    )
    (net (code "28") (name "Net-(C6-Pad-)") (class "Default")
      (node (ref "C6") (pin "-") (pinfunction "-_-") (pintype "passive"))
      (node (ref "R11") (pin "1") (pinfunction "1_1") (pintype "passive"))
    )
    (net (code "29") (name "Net-(C24-Pad-)") (class "Default")
      (node (ref "C24") (pin "-") (pinfunction "-_-") (pintype "passive"))
      (node (ref "R29") (pin "1") (pinfunction "1_1") (pintype "passive"))
    )
    (net (code "30") (name "Net-(IC2A--IN)") (class "Default")
      (node (ref "C1") (pin "1") (pinfunction "1_1") (pintype "passive"))
      (node (ref "IC2") (pin "2") (pinfunction "-IN_2") (pintype "input"))
      (node (ref "R4") (pin "1") (pinfunction "1_1") (pintype "passive"))
      (node (ref "R7") (pin "2") (pinfunction "2_2") (pintype "passive"))
    )
    (net (code "31") (name "Net-(IC2A-OUT)") (class "Default")
      (node (ref "IC2") (pin "1") (pinfunction "OUT_1") (pintype "output"))
      (node (ref "R1") (pin "1") (pinfunction "1_1") (pintype "passive"))
    )
    (net (code "32") (name "Net-(IC2B--IN)") (class "Default")
      (node (ref "C7") (pin "1") (pinfunction "1_1") (pintype "passive"))
      (node (ref "IC2") (pin "6") (pinfunction "-IN_6") (pintype "input"))
      (node (ref "R11") (pin "2") (pinfunction "2_2") (pintype "passive"))
      (node (ref "R15") (pin "1") (pinfunction "1_1") (pintype "passive"))
    )
    (net (code "33") (name "Net-(IC2B-OUT)") (class "Default")
      (node (ref "IC2") (pin "7") (pinfunction "OUT_7") (pintype "output"))
      (node (ref "R35") (pin "1") (pinfunction "1_1") (pintype "passive"))
    )
    (net (code "34") (name "Net-(IC2C--IN)") (class "Default")
      (node (ref "C8") (pin "1") (pinfunction "1_1") (pintype "passive"))
      (node (ref "IC2") (pin "9") (pinfunction "-IN_9") (pintype "input"))
      (node (ref "R10") (pin "2") (pinfunction "2_2") (pintype "passive"))
      (node (ref "R12") (pin "2") (pinfunction "2_2") (pintype "passive"))
      (node (ref "R16") (pin "1") (pinfunction "1_1") (pintype "passive"))
    )
    (net (code "35") (name "Net-(IC2C-OUT)") (class "Default")
      (node (ref "IC2") (pin "8") (pinfunction "OUT_8") (pintype "output"))
      (node (ref "R34") (pin "1") (pinfunction "1_1") (pintype "passive"))
    )
    (net (code "36") (name "Net-(IC2D--IN)") (class "Default")
      (node (ref "IC2") (pin "13") (pinfunction "-IN_13") (pintype "input"))
      (node (ref "IC2") (pin "14") (pinfunction "OUT_14") (pintype "output"))
    )
    (net (code "37") (name "Net-(IC4-AREF)") (class "Default")
      (node (ref "C18") (pin "1") (pinfunction "1_1") (pintype "passive"))
      (node (ref "IC4") (pin "32") (pinfunction "AREF_32") (pintype "passive"))
    )
    (net (code "38") (name "Net-(IC4-XTAL1)") (class "Default")
      (node (ref "C13") (pin "2") (pinfunction "2_2") (pintype "passive"))
      (node (ref "IC4") (pin "13") (pinfunction "XTAL1_13") (pintype "bidirectional"))
      (node (ref "Q2") (pin "1") (pinfunction "1_1") (pintype "passive"))
    )
    (net (code "39") (name "Net-(IC4-XTAL2)") (class "Default")
      (node (ref "C14") (pin "2") (pinfunction "2_2") (pintype "passive"))
      (node (ref "IC4") (pin "12") (pinfunction "XTAL2_12") (pintype "bidirectional"))
      (node (ref "Q2") (pin "2") (pinfunction "2_2") (pintype "passive"))
    )
    (net (code "40") (name "Net-(IC5A-QA)") (class "Default")
      (node (ref "IC5") (pin "15") (pinfunction "QA_15") (pintype "tri_state"))
      (node (ref "R19") (pin "1") (pinfunction "1_1") (pintype "passive"))
    )
    (net (code "41") (name "Net-(IC5A-QB)") (class "Default")
      (node (ref "IC5") (pin "1") (pinfunction "QB_1") (pintype "tri_state"))
      (node (ref "R20") (pin "1") (pinfunction "1_1") (pintype "passive"))
    )
    (net (code "42") (name "Net-(IC5A-QC)") (class "Default")
      (node (ref "IC5") (pin "2") (pinfunction "QC_2") (pintype "tri_state"))
      (node (ref "R21") (pin "1") (pinfunction "1_1") (pintype "passive"))
    )
    (net (code "43") (name "Net-(IC5A-QD)") (class "Default")
      (node (ref "IC5") (pin "3") (pinfunction "QD_3") (pintype "tri_state"))
      (node (ref "R22") (pin "1") (pinfunction "1_1") (pintype "passive"))
    )
    (net (code "44") (name "Net-(IC5A-QE)") (class "Default")
      (node (ref "IC5") (pin "4") (pinfunction "QE_4") (pintype "tri_state"))
      (node (ref "R23") (pin "1") (pinfunction "1_1") (pintype "passive"))
    )
    (net (code "45") (name "Net-(IC5A-QF)") (class "Default")
      (node (ref "IC5") (pin "5") (pinfunction "QF_5") (pintype "tri_state"))
      (node (ref "R24") (pin "1") (pinfunction "1_1") (pintype "passive"))
    )
    (net (code "46") (name "Net-(IC6A-A)") (class "Default")
      (node (ref "IC6") (pin "11") (pinfunction "A_11") (pintype "input"))
      (node (ref "RN1") (pin "7") (pinfunction "7_7") (pintype "passive"))
      (node (ref "S1") (pin "3") (pinfunction "P_3") (pintype "passive"))
      (node (ref "S1") (pin "4") (pinfunction "P1_4") (pintype "passive"))
    )
    (net (code "47") (name "Net-(IC6A-B)") (class "Default")
      (node (ref "IC6") (pin "12") (pinfunction "B_12") (pintype "input"))
      (node (ref "RN1") (pin "6") (pinfunction "6_6") (pintype "passive"))
      (node (ref "S2") (pin "3") (pinfunction "P_3") (pintype "passive"))
      (node (ref "S2") (pin "4") (pinfunction "P1_4") (pintype "passive"))
    )
    (net (code "48") (name "Net-(IC6A-C)") (class "Default")
      (node (ref "IC6") (pin "13") (pinfunction "C_13") (pintype "input"))
      (node (ref "RN1") (pin "5") (pinfunction "5_5") (pintype "passive"))
      (node (ref "S3") (pin "3") (pinfunction "P_3") (pintype "passive"))
      (node (ref "S3") (pin "4") (pinfunction "P1_4") (pintype "passive"))
    )
    (net (code "49") (name "Net-(IC6A-D)") (class "Default")
      (node (ref "IC6") (pin "14") (pinfunction "D_14") (pintype "input"))
      (node (ref "RN1") (pin "4") (pinfunction "4_4") (pintype "passive"))
      (node (ref "S4") (pin "3") (pinfunction "P_3") (pintype "passive"))
      (node (ref "S4") (pin "4") (pinfunction "P1_4") (pintype "passive"))
    )
    (net (code "50") (name "Net-(IC6A-E)") (class "Default")
      (node (ref "IC6") (pin "3") (pinfunction "E_3") (pintype "input"))
      (node (ref "RN1") (pin "3") (pinfunction "3_3") (pintype "passive"))
      (node (ref "S5") (pin "3") (pinfunction "P_3") (pintype "passive"))
      (node (ref "S5") (pin "4") (pinfunction "P1_4") (pintype "passive"))
    )
    (net (code "51") (name "Net-(IC6A-F)") (class "Default")
      (node (ref "IC6") (pin "4") (pinfunction "F_4") (pintype "input"))
      (node (ref "RN1") (pin "2") (pinfunction "2_2") (pintype "passive"))
      (node (ref "S6") (pin "3") (pinfunction "P_3") (pintype "passive"))
      (node (ref "S6") (pin "4") (pinfunction "P1_4") (pintype "passive"))
    )
    (net (code "52") (name "Net-(IC7A--IN)") (class "Default")
      (node (ref "IC7") (pin "2") (pinfunction "-IN_2") (pintype "input"))
      (node (ref "R30") (pin "1") (pinfunction "1_1") (pintype "passive"))
      (node (ref "R32") (pin "2") (pinfunction "2_2") (pintype "passive"))
    )
    (net (code "53") (name "Net-(IC7B-+IN)") (class "Default")
      (node (ref "C25") (pin "1") (pinfunction "1_1") (pintype "passive"))
      (node (ref "IC7") (pin "5") (pinfunction "+IN_5") (pintype "input"))
      (node (ref "R31") (pin "2") (pinfunction "2_2") (pintype "passive"))
      (node (ref "R33") (pin "1") (pinfunction "1_1") (pintype "passive"))
    )
    (net (code "54") (name "Net-(IC7B--IN)") (class "Default")
      (node (ref "C22") (pin "1") (pinfunction "1_1") (pintype "passive"))
      (node (ref "IC7") (pin "6") (pinfunction "-IN_6") (pintype "input"))
      (node (ref "R28") (pin "1") (pinfunction "1_1") (pintype "passive"))
      (node (ref "R29") (pin "2") (pinfunction "2_2") (pintype "passive"))
    )
    (net (code "55") (name "Net-(J1-3)") (class "Default")
      (node (ref "J1") (pin "P3") (pinfunction "3_P3") (pintype "passive"))
      (node (ref "R25") (pin "2") (pinfunction "2_2") (pintype "passive"))
    )
    (net (code "56") (name "Net-(J2-3)") (class "Default")
      (node (ref "J2") (pin "P3") (pinfunction "3_P3") (pintype "passive"))
      (node (ref "R27") (pin "2") (pinfunction "2_2") (pintype "passive"))
    )
    (net (code "57") (name "Net-(J3-3)") (class "Default")
      (node (ref "C8") (pin "2") (pinfunction "2_2") (pintype "passive"))
      (node (ref "J3") (pin "P3") (pinfunction "3_P3") (pintype "passive"))
      (node (ref "R16") (pin "2") (pinfunction "2_2") (pintype "passive"))
      (node (ref "R34") (pin "2") (pinfunction "2_2") (pintype "passive"))
    )
    (net (code "58") (name "Net-(J4-3)") (class "Default")
      (node (ref "C7") (pin "2") (pinfunction "2_2") (pintype "passive"))
      (node (ref "J4") (pin "P3") (pinfunction "3_P3") (pintype "passive"))
      (node (ref "R15") (pin "2") (pinfunction "2_2") (pintype "passive"))
      (node (ref "R35") (pin "2") (pinfunction "2_2") (pintype "passive"))
    )
    (net (code "59") (name "Net-(J5-3)") (class "Default")
      (node (ref "C24") (pin "+") (pinfunction "+_+") (pintype "passive"))
      (node (ref "J5") (pin "P3") (pinfunction "3_P3") (pintype "passive"))
      (node (ref "R32") (pin "1") (pinfunction "1_1") (pintype "passive"))
      (node (ref "R7") (pin "1") (pinfunction "1_1") (pintype "passive"))
    )
    (net (code "60") (name "Net-(J9-Pad1)") (class "Default")
      (node (ref "J9") (pin "1") (pinfunction "1_1") (pintype "passive"))
      (node (ref "JP4") (pin "1") (pinfunction "1_1") (pintype "passive"))
      (node (ref "JP4") (pin "2") (pinfunction "2_2") (pintype "passive"))
    )
    (net (code "61") (name "Net-(J9-Pad3)") (class "Default")
      (node (ref "J9") (pin "3") (pinfunction "3_3") (pintype "passive"))
      (node (ref "JP3") (pin "1") (pinfunction "1_1") (pintype "passive"))
      (node (ref "JP3") (pin "2") (pinfunction "2_2") (pintype "passive"))
    )
    (net (code "62") (name "Net-(J10-3)") (class "Default")
      (node (ref "J10") (pin "P3") (pinfunction "3_P3") (pintype "passive"))
      (node (ref "R18") (pin "1") (pinfunction "1_1") (pintype "passive"))
    )
    (net (code "63") (name "Net-(LED1-PadA)") (class "Default")
      (node (ref "LED1") (pin "A") (pinfunction "A_A") (pintype "passive"))
      (node (ref "R19") (pin "2") (pinfunction "2_2") (pintype "passive"))
    )
    (net (code "64") (name "Net-(LED2-PadA)") (class "Default")
      (node (ref "LED2") (pin "A") (pinfunction "A_A") (pintype "passive"))
      (node (ref "R20") (pin "2") (pinfunction "2_2") (pintype "passive"))
    )
    (net (code "65") (name "Net-(LED3-PadA)") (class "Default")
      (node (ref "LED3") (pin "A") (pinfunction "A_A") (pintype "passive"))
      (node (ref "R21") (pin "2") (pinfunction "2_2") (pintype "passive"))
    )
    (net (code "66") (name "Net-(LED4-PadA)") (class "Default")
      (node (ref "LED4") (pin "A") (pinfunction "A_A") (pintype "passive"))
      (node (ref "R22") (pin "2") (pinfunction "2_2") (pintype "passive"))
    )
    (net (code "67") (name "Net-(LED5-PadA)") (class "Default")
      (node (ref "LED5") (pin "A") (pinfunction "A_A") (pintype "passive"))
      (node (ref "R23") (pin "2") (pinfunction "2_2") (pintype "passive"))
    )
    (net (code "68") (name "Net-(LED6-PadA)") (class "Default")
      (node (ref "LED6") (pin "A") (pinfunction "A_A") (pintype "passive"))
      (node (ref "R24") (pin "2") (pinfunction "2_2") (pintype "passive"))
    )
    (net (code "69") (name "Net-(OK1-A)") (class "Default")
      (node (ref "D1") (pin "C") (pinfunction "C_C") (pintype "passive"))
      (node (ref "OK1") (pin "2") (pinfunction "A_2") (pintype "passive"))
      (node (ref "R3") (pin "2") (pinfunction "2_2") (pintype "passive"))
    )
    (net (code "70") (name "Net-(OK1-C)") (class "Default")
      (node (ref "D1") (pin "A") (pinfunction "A_A") (pintype "passive"))
      (node (ref "OK1") (pin "3") (pinfunction "C_3") (pintype "passive"))
      (node (ref "X1") (pin "5") (pinfunction "5_5") (pintype "passive"))
    )
    (net (code "71") (name "Net-(Q1-B)") (class "Default")
      (node (ref "Q1") (pin "2") (pinfunction "B_2") (pintype "passive"))
      (node (ref "R18") (pin "2") (pinfunction "2_2") (pintype "passive"))
    )
    (net (code "72") (name "Net-(R3-Pad1)") (class "Default")
      (node (ref "R3") (pin "1") (pinfunction "1_1") (pintype "passive"))
      (node (ref "X1") (pin "4") (pinfunction "4_4") (pintype "passive"))
    )
    (net (code "73") (name "Net-(R8-S)") (class "Default")
      (node (ref "R8") (pin "2") (pinfunction "S_2") (pintype "passive"))
      (node (ref "U$3") (pin "3") (pinfunction "VO_3") (pintype "bidirectional"))
    )
    (net (code "74") (name "Net-(R9-E)") (class "Default")
      (node (ref "R6") (pin "1") (pinfunction "1_1") (pintype "passive"))
      (node (ref "R9") (pin "1") (pinfunction "E_1") (pintype "passive"))
    )
    (net (code "75") (name "Net-(R10-Pad1)") (class "Default")
      (node (ref "R10") (pin "1") (pinfunction "1_1") (pintype "passive"))
      (node (ref "R6") (pin "2") (pinfunction "2_2") (pintype "passive"))
    )
    (net (code "76") (name "Net-(R13-E)") (class "Default")
      (node (ref "R12") (pin "1") (pinfunction "1_1") (pintype "passive"))
      (node (ref "R13") (pin "1") (pinfunction "E_1") (pintype "passive"))
    )
    (net (code "77") (name "Net-(U$3-A)") (class "Default")
      (node (ref "R14") (pin "2") (pinfunction "2_2") (pintype "passive"))
      (node (ref "U$3") (pin "15") (pinfunction "A_15") (pintype "power_in"))
    )
    (net (code "78") (name "PITCH_DETECTOR") (class "Default")
      (node (ref "IC4") (pin "20") (pinfunction "(ICP)PD6_20") (pintype "bidirectional"))
      (node (ref "IC7") (pin "1") (pinfunction "OUT_1") (pintype "output"))
      (node (ref "R30") (pin "2") (pinfunction "2_2") (pintype "passive"))
    )
    (net (code "79") (name "REF_-4.096") (class "Default")
      (node (ref "C3") (pin "1") (pinfunction "1_1") (pintype "passive"))
      (node (ref "IC1") (pin "3") (pinfunction "A_3") (pintype "passive"))
      (node (ref "R2") (pin "2") (pinfunction "2_2") (pintype "passive"))
      (node (ref "R9") (pin "2") (pinfunction "S_2") (pintype "passive"))
      (node (ref "R9") (pin "3") (pinfunction "A_3") (pintype "passive"))
    )
    (net (code "80") (name "RESET") (class "Default")
      (node (ref "C20") (pin "1") (pinfunction "1_1") (pintype "passive"))
      (node (ref "IC4") (pin "9") (pinfunction "RESET_9") (pintype "input"))
      (node (ref "R26") (pin "1") (pinfunction "1_1") (pintype "passive"))
      (node (ref "U1") (pin "5") (pinfunction "5_5") (pintype "passive"))
    )
    (net (code "81") (name "SCK") (class "Default")
      (node (ref "IC3") (pin "3") (pinfunction "SCK_3") (pintype "input"))
      (node (ref "IC4") (pin "8") (pinfunction "(SCK)PB7_8") (pintype "bidirectional"))
      (node (ref "U1") (pin "3") (pinfunction "3_3") (pintype "passive"))
    )
    (net (code "82") (name "SS") (class "Default")
      (node (ref "IC3") (pin "2") (pinfunction "#CS_2") (pintype "input"))
      (node (ref "IC4") (pin "5") (pinfunction "(SS)PB4_5") (pintype "bidirectional"))
    )
    (net (code "83") (name "VCC") (class "Default")
      (node (ref "C19") (pin "1") (pinfunction "1_1") (pintype "passive"))
      (node (ref "C27") (pin "+") (pinfunction "+_+") (pintype "passive"))
      (node (ref "C4") (pin "1") (pinfunction "1_1") (pintype "passive"))
      (node (ref "D9") (pin "C") (pinfunction "C_C") (pintype "passive"))
      (node (ref "IC2") (pin "4") (pinfunction "V+_4") (pintype "power_in"))
      (node (ref "IC8") (pin "IN") (pinfunction "IN_IN") (pintype "input"))
      (node (ref "J7") (pin "7") (pinfunction "7_7") (pintype "passive"))
      (node (ref "J7") (pin "8") (pinfunction "8_8") (pintype "passive"))
      (node (ref "JP9") (pin "1") (pinfunction "1_1") (pintype "passive"))
    )
    (net (code "84") (name "VEE") (class "Default")
      (node (ref "C28") (pin "-") (pinfunction "-_-") (pintype "passive"))
      (node (ref "C5") (pin "2") (pinfunction "2_2") (pintype "passive"))
      (node (ref "IC2") (pin "11") (pinfunction "V-_11") (pintype "power_in"))
      (node (ref "J7") (pin "15") (pinfunction "15_15") (pintype "passive"))
      (node (ref "J7") (pin "16") (pinfunction "16_16") (pintype "passive"))
      (node (ref "JP8") (pin "1") (pinfunction "1_1") (pintype "passive"))
      (node (ref "R2") (pin "1") (pinfunction "1_1") (pintype "passive"))
    )
    (net (code "85") (name "unconnected-(IC4-(ADC1)PA1-Pad39)") (class "Default")
      (node (ref "IC4") (pin "39") (pinfunction "(ADC1)PA1_39") (pintype "bidirectional"))
    )
    (net (code "86") (name "unconnected-(IC4-(AIN0{slash}INT2)PB2-Pad3)") (class "Default")
      (node (ref "IC4") (pin "3") (pinfunction "(AIN0/INT2)PB2_3") (pintype "bidirectional"))
    )
    (net (code "87") (name "unconnected-(IC4-(AIN1{slash}OC0)PB3-Pad4)") (class "Default")
      (node (ref "IC4") (pin "4") (pinfunction "(AIN1/OC0)PB3_4") (pintype "bidirectional"))
    )
    (net (code "88") (name "unconnected-(IC4-(OC1A)PD5-Pad19)") (class "Default")
      (node (ref "IC4") (pin "19") (pinfunction "(OC1A)PD5_19") (pintype "bidirectional"))
    )
    (net (code "89") (name "unconnected-(IC4-(OC2)PD7-Pad21)") (class "Default")
      (node (ref "IC4") (pin "21") (pinfunction "(OC2)PD7_21") (pintype "bidirectional"))
    )
    (net (code "90") (name "unconnected-(IC4-(T0{slash}XCK)PB0-Pad1)") (class "Default")
      (node (ref "IC4") (pin "1") (pinfunction "(T0/XCK)PB0_1") (pintype "bidirectional"))
    )
    (net (code "91") (name "unconnected-(IC4-(T1)PB1-Pad2)") (class "Default")
      (node (ref "IC4") (pin "2") (pinfunction "(T1)PB1_2") (pintype "bidirectional"))
    )
    (net (code "92") (name "unconnected-(IC4-(TMS)PC3-Pad25)") (class "Default")
      (node (ref "IC4") (pin "25") (pinfunction "(TMS)PC3_25") (pintype "bidirectional"))
    )
    (net (code "93") (name "unconnected-(IC4-(TXD)PD1-Pad15)") (class "Default")
      (node (ref "IC4") (pin "15") (pinfunction "(TXD)PD1_15") (pintype "bidirectional"))
    )
    (net (code "94") (name "unconnected-(IC5A-QG-Pad6)") (class "Default")
      (node (ref "IC5") (pin "6") (pinfunction "QG_6") (pintype "tri_state"))
    )
    (net (code "95") (name "unconnected-(IC5A-QH*-Pad9)") (class "Default")
      (node (ref "IC5") (pin "9") (pinfunction "QH*_9") (pintype "tri_state"))
    )
    (net (code "96") (name "unconnected-(IC5A-QH-Pad7)") (class "Default")
      (node (ref "IC5") (pin "7") (pinfunction "QH_7") (pintype "tri_state"))
    )
    (net (code "97") (name "unconnected-(IC6A-~{QH}-Pad7)") (class "Default")
      (node (ref "IC6") (pin "7") (pinfunction "~{QH}_7") (pintype "output"))
    )
    (net (code "98") (name "unconnected-(J1-2-PadP2)") (class "Default")
      (node (ref "J1") (pin "P2") (pinfunction "2_P2") (pintype "passive"))
    )
    (net (code "99") (name "unconnected-(J2-2-PadP2)") (class "Default")
      (node (ref "J2") (pin "P2") (pinfunction "2_P2") (pintype "passive"))
    )
    (net (code "100") (name "unconnected-(J3-2-PadP2)") (class "Default")
      (node (ref "J3") (pin "P2") (pinfunction "2_P2") (pintype "passive"))
    )
    (net (code "101") (name "unconnected-(J4-2-PadP2)") (class "Default")
      (node (ref "J4") (pin "P2") (pinfunction "2_P2") (pintype "passive"))
    )
    (net (code "102") (name "unconnected-(J5-2-PadP2)") (class "Default")
      (node (ref "J5") (pin "P2") (pinfunction "2_P2") (pintype "passive"))
    )
    (net (code "103") (name "unconnected-(J7-Pad1)") (class "Default")
      (node (ref "J7") (pin "1") (pinfunction "1_1") (pintype "passive"))
    )
    (net (code "104") (name "unconnected-(J7-Pad2)") (class "Default")
      (node (ref "J7") (pin "2") (pinfunction "2_2") (pintype "passive"))
    )
    (net (code "105") (name "unconnected-(J7-Pad3)") (class "Default")
      (node (ref "J7") (pin "3") (pinfunction "3_3") (pintype "passive"))
    )
    (net (code "106") (name "unconnected-(J7-Pad4)") (class "Default")
      (node (ref "J7") (pin "4") (pinfunction "4_4") (pintype "passive"))
    )
    (net (code "107") (name "unconnected-(J8-PadTN)") (class "Default")
      (node (ref "J8") (pin "TN") (pinfunction "TN_TN") (pintype "passive"))
    )
    (net (code "108") (name "unconnected-(J9-Pad2)") (class "Default")
      (node (ref "J9") (pin "2") (pinfunction "2_2") (pintype "passive"))
    )
    (net (code "109") (name "unconnected-(OK1-VB-Pad7)") (class "Default")
      (node (ref "OK1") (pin "7") (pinfunction "VB_7") (pintype "passive"))
    )
    (net (code "110") (name "unconnected-(U$3-DB0-Pad7)") (class "Default")
      (node (ref "U$3") (pin "7") (pinfunction "DB0_7") (pintype "bidirectional"))
    )
    (net (code "111") (name "unconnected-(U$3-DB1-Pad8)") (class "Default")
      (node (ref "U$3") (pin "8") (pinfunction "DB1_8") (pintype "bidirectional"))
    )
    (net (code "112") (name "unconnected-(U$3-DB2-Pad9)") (class "Default")
      (node (ref "U$3") (pin "9") (pinfunction "DB2_9") (pintype "bidirectional"))
    )
    (net (code "113") (name "unconnected-(U$3-DB3-Pad10)") (class "Default")
      (node (ref "U$3") (pin "10") (pinfunction "DB3_10") (pintype "bidirectional"))
    )
    (net (code "114") (name "unconnected-(X1-Pad1)") (class "Default")
      (node (ref "X1") (pin "1") (pinfunction "1_1") (pintype "passive"))
    )
    (net (code "115") (name "unconnected-(X1-Pad2)") (class "Default")
      (node (ref "X1") (pin "2") (pinfunction "2_2") (pintype "passive"))
    )
    (net (code "116") (name "unconnected-(X1-Pad3)") (class "Default")
      (node (ref "X1") (pin "3") (pinfunction "3_3") (pintype "passive"))
    )
  )
)
